# DCCurrent.net
KiCad netlist of a schematic drawn in EAGLE
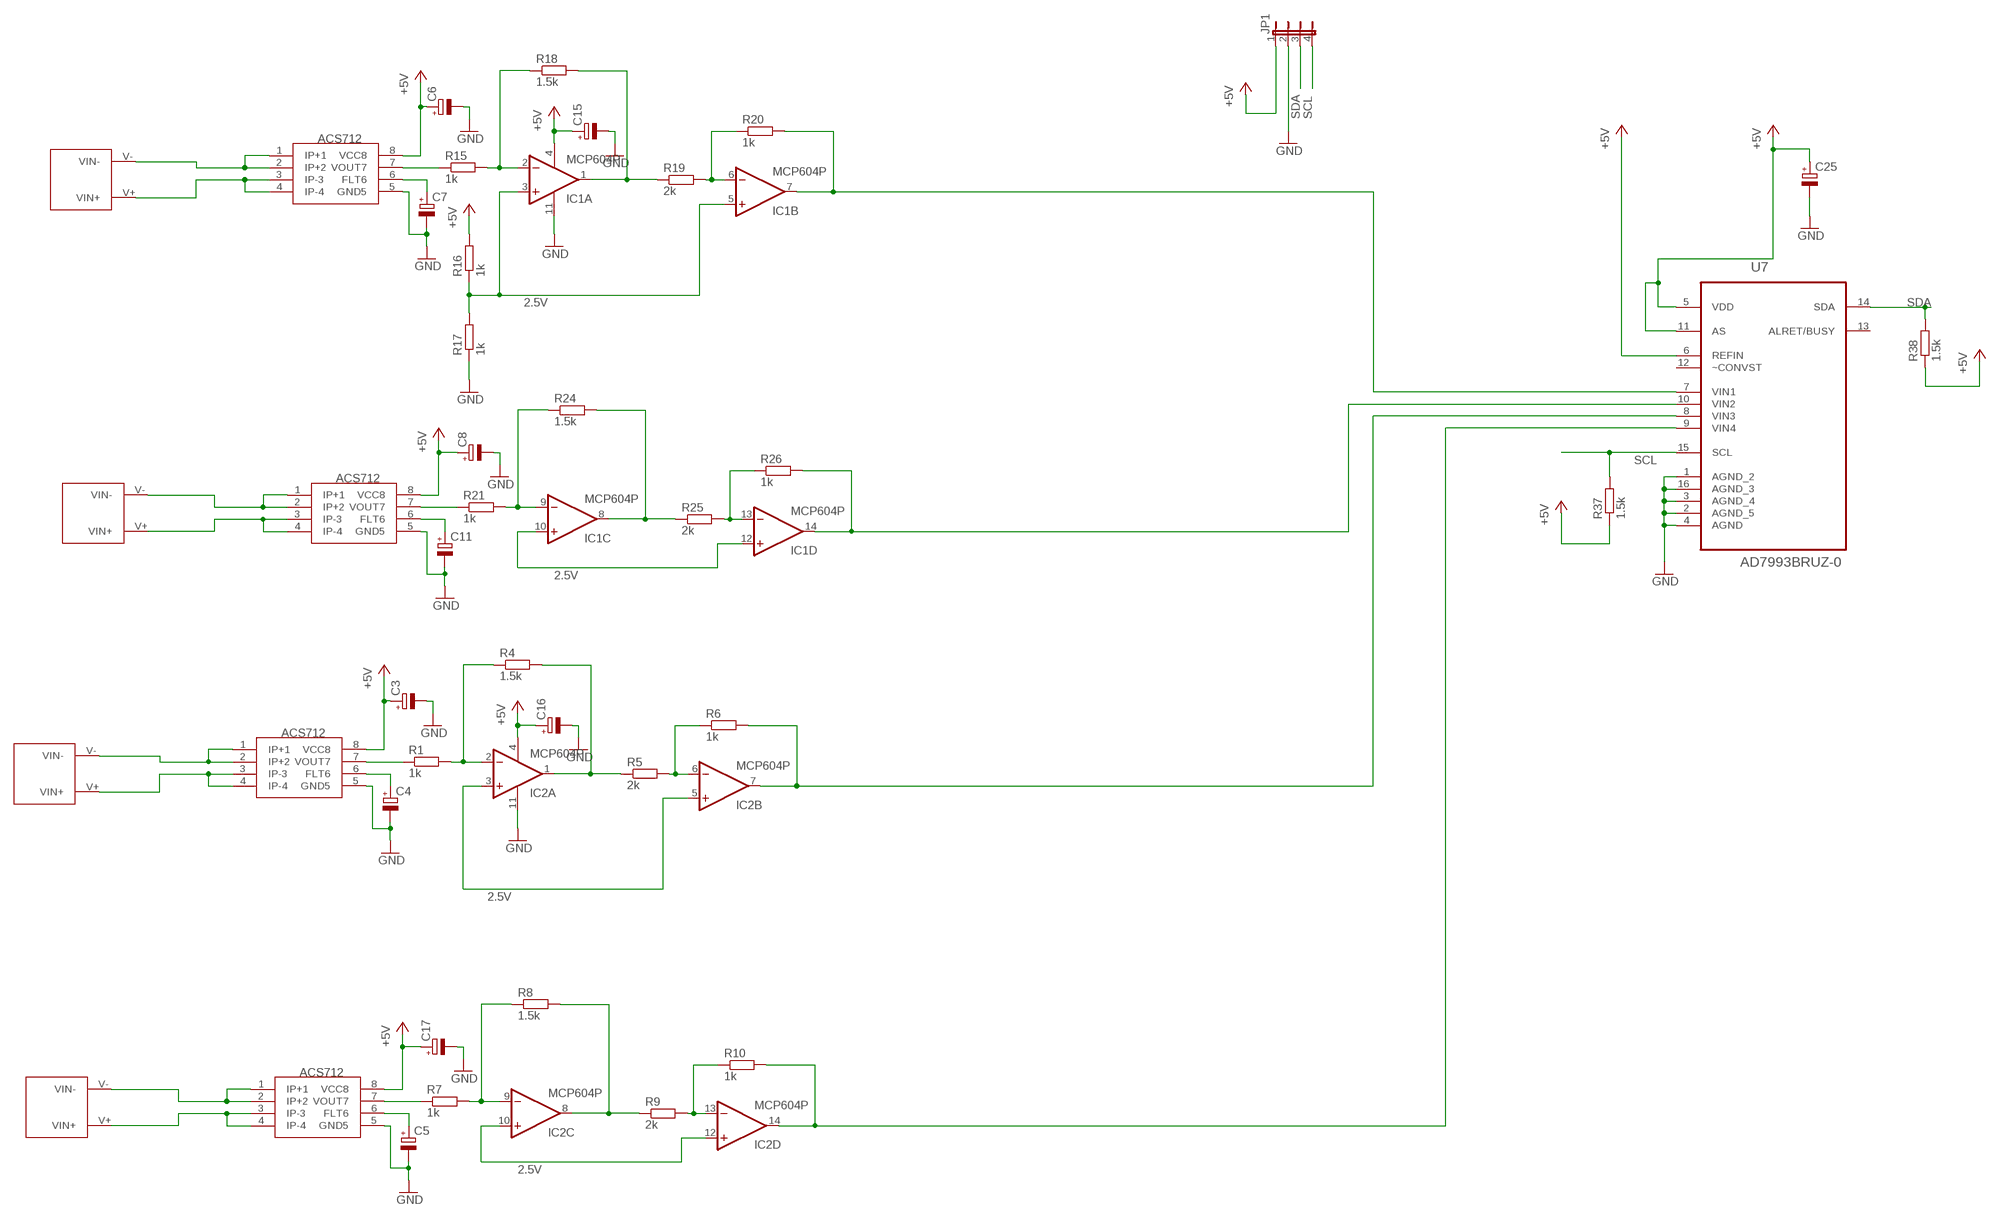
[diagram p0: schematic, sheet 1]

(export (version "E")
  (design (tool "Eeschema 10.0.6"))
  (components
    (comp (ref "C3")
      (value "CPOL-EUE2-4")
      (footprint "eagle-import:E2-4")
      (libsource (lib "eagle-import") (part "CPOL-EUE2-4"))
    )
    (comp (ref "C4")
      (value "CPOL-EUE2-4")
      (footprint "eagle-import:E2-4")
      (libsource (lib "eagle-import") (part "CPOL-EUE2-4"))
    )
    (comp (ref "C5")
      (value "CPOL-EUE2-4")
      (footprint "eagle-import:E2-4")
      (libsource (lib "eagle-import") (part "CPOL-EUE2-4"))
    )
    (comp (ref "C6")
      (value "CPOL-EUE2-4")
      (footprint "eagle-import:E2-4")
      (libsource (lib "eagle-import") (part "CPOL-EUE2-4"))
    )
    (comp (ref "C7")
      (value "CPOL-EUE2-4")
      (footprint "eagle-import:E2-4")
      (libsource (lib "eagle-import") (part "CPOL-EUE2-4"))
    )
    (comp (ref "C8")
      (value "CPOL-EUE2-4")
      (footprint "eagle-import:E2-4")
      (libsource (lib "eagle-import") (part "CPOL-EUE2-4"))
    )
    (comp (ref "C11")
      (value "CPOL-EUE2-4")
      (footprint "eagle-import:E2-4")
      (libsource (lib "eagle-import") (part "CPOL-EUE2-4"))
    )
    (comp (ref "C15")
      (value "CPOL-EUE2-4")
      (footprint "eagle-import:E2-4")
      (libsource (lib "eagle-import") (part "CPOL-EUE2-4"))
    )
    (comp (ref "C16")
      (value "CPOL-EUE2-4")
      (footprint "eagle-import:E2-4")
      (libsource (lib "eagle-import") (part "CPOL-EUE2-4"))
    )
    (comp (ref "C17")
      (value "CPOL-EUE2-4")
      (footprint "eagle-import:E2-4")
      (libsource (lib "eagle-import") (part "CPOL-EUE2-4"))
    )
    (comp (ref "C25")
      (value "CPOL-EUE2-4")
      (footprint "eagle-import:E2-4")
      (libsource (lib "eagle-import") (part "CPOL-EUE2-4"))
    )
    (comp (ref "IC1")
      (value "MCP604P")
      (footprint "eagle-import:DIL14")
      (libsource (lib "eagle-import") (part "MCP604P"))
    )
    (comp (ref "IC2")
      (value "MCP604P")
      (footprint "eagle-import:DIL14")
      (libsource (lib "eagle-import") (part "MCP604P"))
    )
    (comp (ref "JP1")
      (value "JP4E")
      (footprint "eagle-import:JP4")
      (libsource (lib "eagle-import") (part "JP4E"))
    )
    (comp (ref "R1")
      (value "1k")
      (footprint "eagle-import:0309_12")
      (libsource (lib "eagle-import") (part "R-EU_0309/12"))
    )
    (comp (ref "R4")
      (value "1.5k")
      (footprint "eagle-import:0309_12")
      (libsource (lib "eagle-import") (part "R-EU_0309/12"))
    )
    (comp (ref "R5")
      (value "2k")
      (footprint "eagle-import:0309_12")
      (libsource (lib "eagle-import") (part "R-EU_0309/12"))
    )
    (comp (ref "R6")
      (value "1k")
      (footprint "eagle-import:0309_12")
      (libsource (lib "eagle-import") (part "R-EU_0309/12"))
    )
    (comp (ref "R7")
      (value "1k")
      (footprint "eagle-import:0309_12")
      (libsource (lib "eagle-import") (part "R-EU_0309/12"))
    )
    (comp (ref "R8")
      (value "1.5k")
      (footprint "eagle-import:0309_12")
      (libsource (lib "eagle-import") (part "R-EU_0309/12"))
    )
    (comp (ref "R9")
      (value "2k")
      (footprint "eagle-import:0309_12")
      (libsource (lib "eagle-import") (part "R-EU_0309/12"))
    )
    (comp (ref "R10")
      (value "1k")
      (footprint "eagle-import:0309_12")
      (libsource (lib "eagle-import") (part "R-EU_0309/12"))
    )
    (comp (ref "R15")
      (value "1k")
      (footprint "eagle-import:0309_12")
      (libsource (lib "eagle-import") (part "R-EU_0309/12"))
    )
    (comp (ref "R16")
      (value "1k")
      (footprint "eagle-import:0309_12")
      (libsource (lib "eagle-import") (part "R-EU_0309/12"))
    )
    (comp (ref "R17")
      (value "1k")
      (footprint "eagle-import:0309_12")
      (libsource (lib "eagle-import") (part "R-EU_0309/12"))
    )
    (comp (ref "R18")
      (value "1.5k")
      (footprint "eagle-import:0309_12")
      (libsource (lib "eagle-import") (part "R-EU_0309/12"))
    )
    (comp (ref "R19")
      (value "2k")
      (footprint "eagle-import:0309_12")
      (libsource (lib "eagle-import") (part "R-EU_0309/12"))
    )
    (comp (ref "R20")
      (value "1k")
      (footprint "eagle-import:0309_12")
      (libsource (lib "eagle-import") (part "R-EU_0309/12"))
    )
    (comp (ref "R21")
      (value "1k")
      (footprint "eagle-import:0309_12")
      (libsource (lib "eagle-import") (part "R-EU_0309/12"))
    )
    (comp (ref "R24")
      (value "1.5k")
      (footprint "eagle-import:0309_12")
      (libsource (lib "eagle-import") (part "R-EU_0309/12"))
    )
    (comp (ref "R25")
      (value "2k")
      (footprint "eagle-import:0309_12")
      (libsource (lib "eagle-import") (part "R-EU_0309/12"))
    )
    (comp (ref "R26")
      (value "1k")
      (footprint "eagle-import:0309_12")
      (libsource (lib "eagle-import") (part "R-EU_0309/12"))
    )
    (comp (ref "R37")
      (value "1.5k")
      (footprint "eagle-import:0309_12")
      (libsource (lib "eagle-import") (part "R-EU_0309/12"))
    )
    (comp (ref "R38")
      (value "1.5k")
      (footprint "eagle-import:0309_12")
      (libsource (lib "eagle-import") (part "R-EU_0309/12"))
    )
    (comp (ref "U$1")
      (value "ACS712")
      (footprint "eagle-import:SOIC8")
      (libsource (lib "eagle-import") (part "ACS712"))
    )
    (comp (ref "U$2")
      (value "INPUT_VOLTAGE_CONNECTOR")
      (footprint "eagle-import:INPUT_VOLTAGE_CONNECTOR")
      (libsource (lib "eagle-import") (part "INPUT_VOLTAGE_CONNECTOR"))
    )
    (comp (ref "U$3")
      (value "INPUT_VOLTAGE_CONNECTOR")
      (footprint "eagle-import:INPUT_VOLTAGE_CONNECTOR")
      (libsource (lib "eagle-import") (part "INPUT_VOLTAGE_CONNECTOR"))
    )
    (comp (ref "U$4")
      (value "ACS712")
      (footprint "eagle-import:SOIC8")
      (libsource (lib "eagle-import") (part "ACS712"))
    )
    (comp (ref "U$5")
      (value "INPUT_VOLTAGE_CONNECTOR")
      (footprint "eagle-import:INPUT_VOLTAGE_CONNECTOR")
      (libsource (lib "eagle-import") (part "INPUT_VOLTAGE_CONNECTOR"))
    )
    (comp (ref "U$6")
      (value "INPUT_VOLTAGE_CONNECTOR")
      (footprint "eagle-import:INPUT_VOLTAGE_CONNECTOR")
      (libsource (lib "eagle-import") (part "INPUT_VOLTAGE_CONNECTOR"))
    )
    (comp (ref "U$9")
      (value "ACS712")
      (footprint "eagle-import:SOIC8")
      (libsource (lib "eagle-import") (part "ACS712"))
    )
    (comp (ref "U$11")
      (value "ACS712")
      (footprint "eagle-import:SOIC8")
      (libsource (lib "eagle-import") (part "ACS712"))
    )
    (comp (ref "U7")
      (value "AD7993BRUZ-0")
      (footprint "eagle-import:SOP65P640X120-16N")
      (libsource (lib "eagle-import") (part "AD7993BRUZ-0"))
    )
  )
  (nets
    (net (code "1") (name "+5V") (class "Default")
      (node (ref "C15") (pin "+") (pinfunction "+_+") (pintype "passive"))
      (node (ref "C16") (pin "+") (pinfunction "+_+") (pintype "passive"))
      (node (ref "C17") (pin "+") (pinfunction "+_+") (pintype "passive"))
      (node (ref "C25") (pin "+") (pinfunction "+_+") (pintype "passive"))
      (node (ref "C3") (pin "+") (pinfunction "+_+") (pintype "passive"))
      (node (ref "C6") (pin "+") (pinfunction "+_+") (pintype "passive"))
      (node (ref "C8") (pin "+") (pinfunction "+_+") (pintype "passive"))
      (node (ref "IC1") (pin "4") (pinfunction "V+_4") (pintype "power_in"))
      (node (ref "IC2") (pin "4") (pinfunction "V+_4") (pintype "power_in"))
      (node (ref "JP1") (pin "1") (pinfunction "1_1") (pintype "passive"))
      (node (ref "R16") (pin "2") (pinfunction "2_2") (pintype "passive"))
      (node (ref "R37") (pin "1") (pinfunction "1_1") (pintype "passive"))
      (node (ref "R38") (pin "1") (pinfunction "1_1") (pintype "passive"))
      (node (ref "U$1") (pin "8") (pinfunction "VCC8_8") (pintype "power_in"))
      (node (ref "U$11") (pin "8") (pinfunction "VCC8_8") (pintype "power_in"))
      (node (ref "U$4") (pin "8") (pinfunction "VCC8_8") (pintype "power_in"))
      (node (ref "U$9") (pin "8") (pinfunction "VCC8_8") (pintype "power_in"))
      (node (ref "U7") (pin "11") (pinfunction "AS_11") (pintype "input"))
      (node (ref "U7") (pin "5") (pinfunction "VDD_5") (pintype "power_in"))
      (node (ref "U7") (pin "6") (pinfunction "REFIN_6") (pintype "input"))
    )
    (net (code "2") (name "/2.5V") (class "Default")
      (node (ref "IC1") (pin "10") (pinfunction "+IN_10") (pintype "input"))
      (node (ref "IC1") (pin "12") (pinfunction "+IN_12") (pintype "input"))
      (node (ref "IC1") (pin "3") (pinfunction "+IN_3") (pintype "input"))
      (node (ref "IC1") (pin "5") (pinfunction "+IN_5") (pintype "input"))
      (node (ref "IC2") (pin "10") (pinfunction "+IN_10") (pintype "input"))
      (node (ref "IC2") (pin "12") (pinfunction "+IN_12") (pintype "input"))
      (node (ref "IC2") (pin "3") (pinfunction "+IN_3") (pintype "input"))
      (node (ref "IC2") (pin "5") (pinfunction "+IN_5") (pintype "input"))
      (node (ref "R16") (pin "1") (pinfunction "1_1") (pintype "passive"))
      (node (ref "R17") (pin "2") (pinfunction "2_2") (pintype "passive"))
    )
    (net (code "3") (name "/SCL") (class "Default")
      (node (ref "JP1") (pin "4") (pinfunction "4_4") (pintype "passive"))
      (node (ref "R37") (pin "2") (pinfunction "2_2") (pintype "passive"))
      (node (ref "U7") (pin "15") (pinfunction "SCL_15") (pintype "input"))
    )
    (net (code "4") (name "/SDA") (class "Default")
      (node (ref "JP1") (pin "3") (pinfunction "3_3") (pintype "passive"))
      (node (ref "R38") (pin "2") (pinfunction "2_2") (pintype "passive"))
      (node (ref "U7") (pin "14") (pinfunction "SDA_14") (pintype "bidirectional"))
    )
    (net (code "5") (name "GND") (class "Default")
      (node (ref "C11") (pin "-") (pinfunction "-_-") (pintype "passive"))
      (node (ref "C15") (pin "-") (pinfunction "-_-") (pintype "passive"))
      (node (ref "C16") (pin "-") (pinfunction "-_-") (pintype "passive"))
      (node (ref "C17") (pin "-") (pinfunction "-_-") (pintype "passive"))
      (node (ref "C25") (pin "-") (pinfunction "-_-") (pintype "passive"))
      (node (ref "C3") (pin "-") (pinfunction "-_-") (pintype "passive"))
      (node (ref "C4") (pin "-") (pinfunction "-_-") (pintype "passive"))
      (node (ref "C5") (pin "-") (pinfunction "-_-") (pintype "passive"))
      (node (ref "C6") (pin "-") (pinfunction "-_-") (pintype "passive"))
      (node (ref "C7") (pin "-") (pinfunction "-_-") (pintype "passive"))
      (node (ref "C8") (pin "-") (pinfunction "-_-") (pintype "passive"))
      (node (ref "IC1") (pin "11") (pinfunction "V-_11") (pintype "power_in"))
      (node (ref "IC2") (pin "11") (pinfunction "V-_11") (pintype "power_in"))
      (node (ref "JP1") (pin "2") (pinfunction "2_2") (pintype "passive"))
      (node (ref "R17") (pin "1") (pinfunction "1_1") (pintype "passive"))
      (node (ref "U$1") (pin "5") (pinfunction "GND5_5") (pintype "power_in"))
      (node (ref "U$11") (pin "5") (pinfunction "GND5_5") (pintype "power_in"))
      (node (ref "U$4") (pin "5") (pinfunction "GND5_5") (pintype "power_in"))
      (node (ref "U$9") (pin "5") (pinfunction "GND5_5") (pintype "power_in"))
      (node (ref "U7") (pin "1") (pinfunction "AGND_2_1") (pintype "passive"))
      (node (ref "U7") (pin "16") (pinfunction "AGND_3_16") (pintype "passive"))
      (node (ref "U7") (pin "2") (pinfunction "AGND_5_2") (pintype "passive"))
      (node (ref "U7") (pin "3") (pinfunction "AGND_4_3") (pintype "passive"))
      (node (ref "U7") (pin "4") (pinfunction "AGND_4") (pintype "passive"))
    )
    (net (code "6") (name "Net-(IC1A--IN)") (class "Default")
      (node (ref "IC1") (pin "2") (pinfunction "-IN_2") (pintype "input"))
      (node (ref "R15") (pin "2") (pinfunction "2_2") (pintype "passive"))
      (node (ref "R18") (pin "1") (pinfunction "1_1") (pintype "passive"))
    )
    (net (code "7") (name "Net-(IC1A-OUT)") (class "Default")
      (node (ref "IC1") (pin "1") (pinfunction "OUT_1") (pintype "output"))
      (node (ref "R18") (pin "2") (pinfunction "2_2") (pintype "passive"))
      (node (ref "R19") (pin "1") (pinfunction "1_1") (pintype "passive"))
    )
    (net (code "8") (name "Net-(IC1B--IN)") (class "Default")
      (node (ref "IC1") (pin "6") (pinfunction "-IN_6") (pintype "input"))
      (node (ref "R19") (pin "2") (pinfunction "2_2") (pintype "passive"))
      (node (ref "R20") (pin "1") (pinfunction "1_1") (pintype "passive"))
    )
    (net (code "9") (name "Net-(IC1B-OUT)") (class "Default")
      (node (ref "IC1") (pin "7") (pinfunction "OUT_7") (pintype "output"))
      (node (ref "R20") (pin "2") (pinfunction "2_2") (pintype "passive"))
      (node (ref "U7") (pin "7") (pinfunction "VIN1_7") (pintype "input"))
    )
    (net (code "10") (name "Net-(IC1C--IN)") (class "Default")
      (node (ref "IC1") (pin "9") (pinfunction "-IN_9") (pintype "input"))
      (node (ref "R21") (pin "2") (pinfunction "2_2") (pintype "passive"))
      (node (ref "R24") (pin "1") (pinfunction "1_1") (pintype "passive"))
    )
    (net (code "11") (name "Net-(IC1C-OUT)") (class "Default")
      (node (ref "IC1") (pin "8") (pinfunction "OUT_8") (pintype "output"))
      (node (ref "R24") (pin "2") (pinfunction "2_2") (pintype "passive"))
      (node (ref "R25") (pin "1") (pinfunction "1_1") (pintype "passive"))
    )
    (net (code "12") (name "Net-(IC1D--IN)") (class "Default")
      (node (ref "IC1") (pin "13") (pinfunction "-IN_13") (pintype "input"))
      (node (ref "R25") (pin "2") (pinfunction "2_2") (pintype "passive"))
      (node (ref "R26") (pin "1") (pinfunction "1_1") (pintype "passive"))
    )
    (net (code "13") (name "Net-(IC1D-OUT)") (class "Default")
      (node (ref "IC1") (pin "14") (pinfunction "OUT_14") (pintype "output"))
      (node (ref "R26") (pin "2") (pinfunction "2_2") (pintype "passive"))
      (node (ref "U7") (pin "10") (pinfunction "VIN2_10") (pintype "input"))
    )
    (net (code "14") (name "Net-(IC2A--IN)") (class "Default")
      (node (ref "IC2") (pin "2") (pinfunction "-IN_2") (pintype "input"))
      (node (ref "R1") (pin "2") (pinfunction "2_2") (pintype "passive"))
      (node (ref "R4") (pin "1") (pinfunction "1_1") (pintype "passive"))
    )
    (net (code "15") (name "Net-(IC2A-OUT)") (class "Default")
      (node (ref "IC2") (pin "1") (pinfunction "OUT_1") (pintype "output"))
      (node (ref "R4") (pin "2") (pinfunction "2_2") (pintype "passive"))
      (node (ref "R5") (pin "1") (pinfunction "1_1") (pintype "passive"))
    )
    (net (code "16") (name "Net-(IC2B--IN)") (class "Default")
      (node (ref "IC2") (pin "6") (pinfunction "-IN_6") (pintype "input"))
      (node (ref "R5") (pin "2") (pinfunction "2_2") (pintype "passive"))
      (node (ref "R6") (pin "1") (pinfunction "1_1") (pintype "passive"))
    )
    (net (code "17") (name "Net-(IC2B-OUT)") (class "Default")
      (node (ref "IC2") (pin "7") (pinfunction "OUT_7") (pintype "output"))
      (node (ref "R6") (pin "2") (pinfunction "2_2") (pintype "passive"))
      (node (ref "U7") (pin "8") (pinfunction "VIN3_8") (pintype "input"))
    )
    (net (code "18") (name "Net-(IC2C--IN)") (class "Default")
      (node (ref "IC2") (pin "9") (pinfunction "-IN_9") (pintype "input"))
      (node (ref "R7") (pin "2") (pinfunction "2_2") (pintype "passive"))
      (node (ref "R8") (pin "1") (pinfunction "1_1") (pintype "passive"))
    )
    (net (code "19") (name "Net-(IC2C-OUT)") (class "Default")
      (node (ref "IC2") (pin "8") (pinfunction "OUT_8") (pintype "output"))
      (node (ref "R8") (pin "2") (pinfunction "2_2") (pintype "passive"))
      (node (ref "R9") (pin "1") (pinfunction "1_1") (pintype "passive"))
    )
    (net (code "20") (name "Net-(IC2D--IN)") (class "Default")
      (node (ref "IC2") (pin "13") (pinfunction "-IN_13") (pintype "input"))
      (node (ref "R10") (pin "1") (pinfunction "1_1") (pintype "passive"))
      (node (ref "R9") (pin "2") (pinfunction "2_2") (pintype "passive"))
    )
    (net (code "21") (name "Net-(IC2D-OUT)") (class "Default")
      (node (ref "IC2") (pin "14") (pinfunction "OUT_14") (pintype "output"))
      (node (ref "R10") (pin "2") (pinfunction "2_2") (pintype "passive"))
      (node (ref "U7") (pin "9") (pinfunction "VIN4_9") (pintype "input"))
    )
    (net (code "22") (name "Net-(U$1-FLT6)") (class "Default")
      (node (ref "C4") (pin "+") (pinfunction "+_+") (pintype "passive"))
      (node (ref "U$1") (pin "6") (pinfunction "FLT6_6") (pintype "passive"))
    )
    (net (code "23") (name "Net-(U$1-IP+1)") (class "Default")
      (node (ref "U$1") (pin "1") (pinfunction "IP+1_1") (pintype "bidirectional"))
      (node (ref "U$1") (pin "2") (pinfunction "IP+2_2") (pintype "bidirectional"))
      (node (ref "U$6") (pin "V-") (pinfunction "VIN-_V-") (pintype "bidirectional"))
    )
    (net (code "24") (name "Net-(U$1-IP-3)") (class "Default")
      (node (ref "U$1") (pin "3") (pinfunction "IP-3_3") (pintype "bidirectional"))
      (node (ref "U$1") (pin "4") (pinfunction "IP-4_4") (pintype "bidirectional"))
      (node (ref "U$6") (pin "V+") (pinfunction "VIN+_V+") (pintype "bidirectional"))
    )
    (net (code "25") (name "Net-(U$1-VOUT7)") (class "Default")
      (node (ref "R1") (pin "1") (pinfunction "1_1") (pintype "passive"))
      (node (ref "U$1") (pin "7") (pinfunction "VOUT7_7") (pintype "output"))
    )
    (net (code "26") (name "Net-(U$3-VIN+)") (class "Default")
      (node (ref "U$3") (pin "V+") (pinfunction "VIN+_V+") (pintype "bidirectional"))
      (node (ref "U$9") (pin "3") (pinfunction "IP-3_3") (pintype "bidirectional"))
      (node (ref "U$9") (pin "4") (pinfunction "IP-4_4") (pintype "bidirectional"))
    )
    (net (code "27") (name "Net-(U$3-VIN-)") (class "Default")
      (node (ref "U$3") (pin "V-") (pinfunction "VIN-_V-") (pintype "bidirectional"))
      (node (ref "U$9") (pin "1") (pinfunction "IP+1_1") (pintype "bidirectional"))
      (node (ref "U$9") (pin "2") (pinfunction "IP+2_2") (pintype "bidirectional"))
    )
    (net (code "28") (name "Net-(U$4-FLT6)") (class "Default")
      (node (ref "C5") (pin "+") (pinfunction "+_+") (pintype "passive"))
      (node (ref "U$4") (pin "6") (pinfunction "FLT6_6") (pintype "passive"))
    )
    (net (code "29") (name "Net-(U$4-IP+1)") (class "Default")
      (node (ref "U$4") (pin "1") (pinfunction "IP+1_1") (pintype "bidirectional"))
      (node (ref "U$4") (pin "2") (pinfunction "IP+2_2") (pintype "bidirectional"))
      (node (ref "U$5") (pin "V-") (pinfunction "VIN-_V-") (pintype "bidirectional"))
    )
    (net (code "30") (name "Net-(U$4-IP-3)") (class "Default")
      (node (ref "U$4") (pin "3") (pinfunction "IP-3_3") (pintype "bidirectional"))
      (node (ref "U$4") (pin "4") (pinfunction "IP-4_4") (pintype "bidirectional"))
      (node (ref "U$5") (pin "V+") (pinfunction "VIN+_V+") (pintype "bidirectional"))
    )
    (net (code "31") (name "Net-(U$4-VOUT7)") (class "Default")
      (node (ref "R7") (pin "1") (pinfunction "1_1") (pintype "passive"))
      (node (ref "U$4") (pin "7") (pinfunction "VOUT7_7") (pintype "output"))
    )
    (net (code "32") (name "Net-(U$9-FLT6)") (class "Default")
      (node (ref "C7") (pin "+") (pinfunction "+_+") (pintype "passive"))
      (node (ref "U$9") (pin "6") (pinfunction "FLT6_6") (pintype "passive"))
    )
    (net (code "33") (name "Net-(U$9-VOUT7)") (class "Default")
      (node (ref "R15") (pin "1") (pinfunction "1_1") (pintype "passive"))
      (node (ref "U$9") (pin "7") (pinfunction "VOUT7_7") (pintype "output"))
    )
    (net (code "34") (name "Net-(U$11-FLT6)") (class "Default")
      (node (ref "C11") (pin "+") (pinfunction "+_+") (pintype "passive"))
      (node (ref "U$11") (pin "6") (pinfunction "FLT6_6") (pintype "passive"))
    )
    (net (code "35") (name "Net-(U$11-IP+1)") (class "Default")
      (node (ref "U$11") (pin "1") (pinfunction "IP+1_1") (pintype "bidirectional"))
      (node (ref "U$11") (pin "2") (pinfunction "IP+2_2") (pintype "bidirectional"))
      (node (ref "U$2") (pin "V-") (pinfunction "VIN-_V-") (pintype "bidirectional"))
    )
    (net (code "36") (name "Net-(U$11-IP-3)") (class "Default")
      (node (ref "U$11") (pin "3") (pinfunction "IP-3_3") (pintype "bidirectional"))
      (node (ref "U$11") (pin "4") (pinfunction "IP-4_4") (pintype "bidirectional"))
      (node (ref "U$2") (pin "V+") (pinfunction "VIN+_V+") (pintype "bidirectional"))
    )
    (net (code "37") (name "Net-(U$11-VOUT7)") (class "Default")
      (node (ref "R21") (pin "1") (pinfunction "1_1") (pintype "passive"))
      (node (ref "U$11") (pin "7") (pinfunction "VOUT7_7") (pintype "output"))
    )
    (net (code "38") (name "unconnected-(U7-ALRET{slash}BUSY-Pad13)") (class "Default")
      (node (ref "U7") (pin "13") (pinfunction "ALRET/BUSY_13") (pintype "output"))
    )
    (net (code "39") (name "unconnected-(U7-~{CONVST}-Pad12)") (class "Default")
      (node (ref "U7") (pin "12") (pinfunction "~{CONVST}_12") (pintype "input"))
    )
  )
)
